# stepper-encoder-lcd.net
KiCad netlist of a schematic drawn in Altium Designer
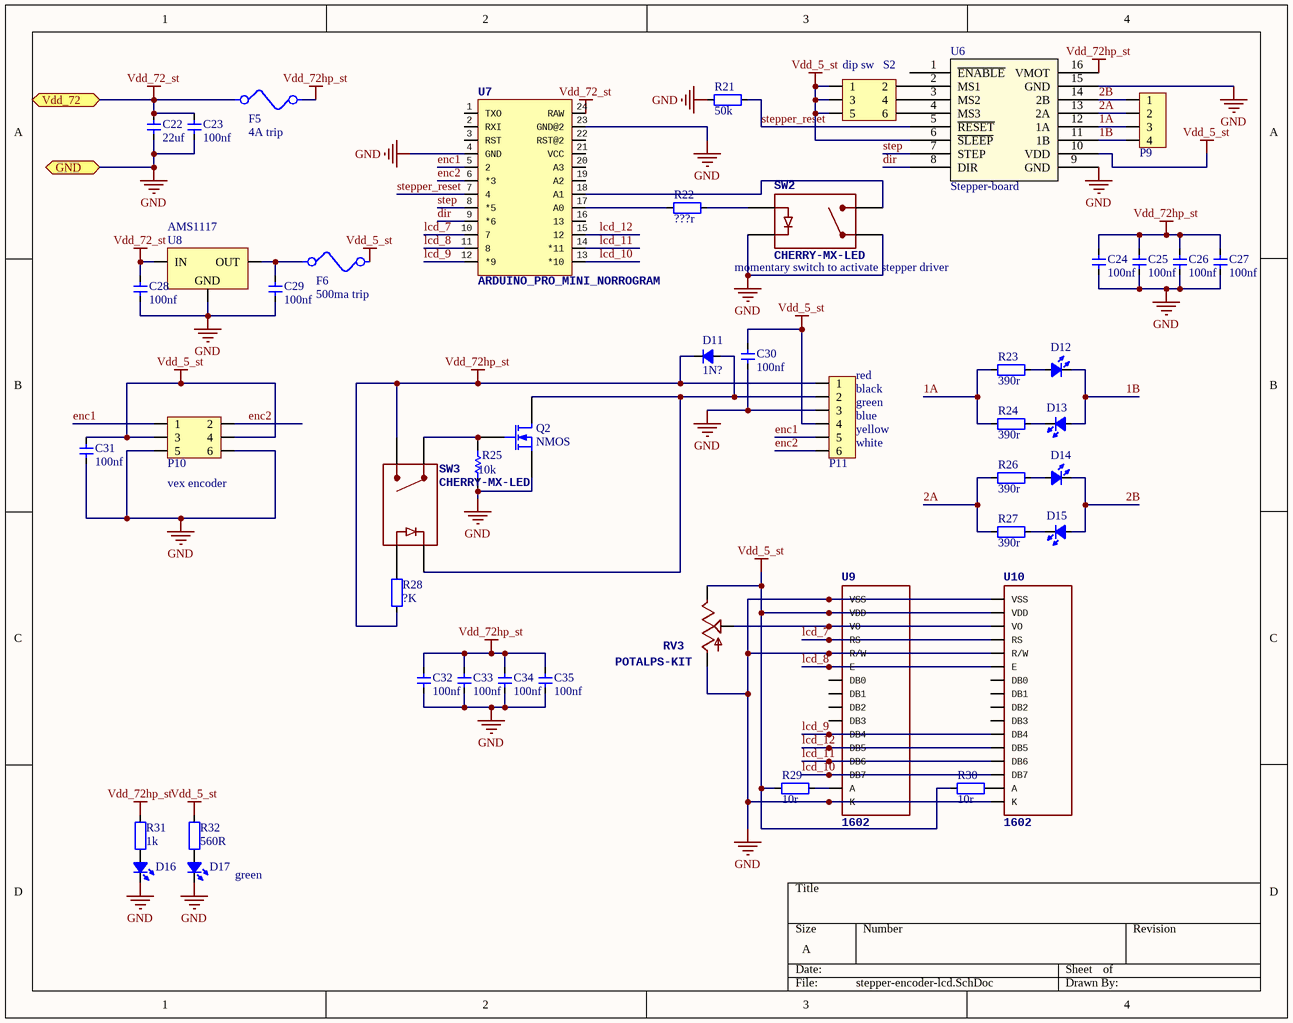
[diagram p0: stepper-encoder-lcd.SchDoc]

(export (version "E")
  (design (tool "Eeschema 10.0.6"))
  (components
    (comp (ref "C22")
      (value "22uf")
      (footprint "PCB_PassiveCap:CAP_0805")
      (description "Capacitor")
      (fields (field (name "Comment") "Cap_0805"))
      (libsource (lib "SCH_Passive") (part "Cap_0805"))
    )
    (comp (ref "C23")
      (value "100nf")
      (footprint "PCB_PassiveCap:CAP_0805")
      (description "Capacitor")
      (fields (field (name "Comment") "Cap_0805"))
      (libsource (lib "SCH_Passive") (part "Cap_0805"))
    )
    (comp (ref "C24")
      (value "100nf")
      (footprint "PCB_PassiveCap:CAP_0805")
      (description "Capacitor")
      (fields (field (name "Comment") "Cap_0805"))
      (libsource (lib "SCH_Passive") (part "Cap_0805"))
    )
    (comp (ref "C25")
      (value "100nf")
      (footprint "PCB_PassiveCap:CAP_0805")
      (description "Capacitor")
      (fields (field (name "Comment") "Cap_0805"))
      (libsource (lib "SCH_Passive") (part "Cap_0805"))
    )
    (comp (ref "C26")
      (value "100nf")
      (footprint "PCB_PassiveCap:CAP_0805")
      (description "Capacitor")
      (fields (field (name "Comment") "Cap_0805"))
      (libsource (lib "SCH_Passive") (part "Cap_0805"))
    )
    (comp (ref "C27")
      (value "100nf")
      (footprint "PCB_PassiveCap:CAP_0805")
      (description "Capacitor")
      (fields (field (name "Comment") "Cap_0805"))
      (libsource (lib "SCH_Passive") (part "Cap_0805"))
    )
    (comp (ref "C28")
      (value "100nf")
      (footprint "PCB_PassiveCap:CAP_0805")
      (description "Capacitor")
      (fields (field (name "Comment") "Cap_0805"))
      (libsource (lib "SCH_Passive") (part "Cap_0805"))
    )
    (comp (ref "C29")
      (value "100nf")
      (footprint "PCB_PassiveCap:CAP_0805")
      (description "Capacitor")
      (fields (field (name "Comment") "Cap_0805"))
      (libsource (lib "SCH_Passive") (part "Cap_0805"))
    )
    (comp (ref "C30")
      (value "100nf")
      (footprint "PCB_PassiveCap:CAP_0805")
      (description "Capacitor")
      (fields (field (name "Comment") "Cap_0805"))
      (libsource (lib "SCH_Passive") (part "Cap_0805"))
    )
    (comp (ref "C31")
      (value "100nf")
      (footprint "PCB_PassiveCap:CAP_0805")
      (description "Capacitor")
      (fields (field (name "Comment") "Cap_0805"))
      (libsource (lib "SCH_Passive") (part "Cap_0805"))
    )
    (comp (ref "C32")
      (value "100nf")
      (footprint "PCB_PassiveCap:CAP_0805")
      (description "Capacitor")
      (fields (field (name "Comment") "Cap_0805"))
      (libsource (lib "SCH_Passive") (part "Cap_0805"))
    )
    (comp (ref "C33")
      (value "100nf")
      (footprint "PCB_PassiveCap:CAP_0805")
      (description "Capacitor")
      (fields (field (name "Comment") "Cap_0805"))
      (libsource (lib "SCH_Passive") (part "Cap_0805"))
    )
    (comp (ref "C34")
      (value "100nf")
      (footprint "PCB_PassiveCap:CAP_0805")
      (description "Capacitor")
      (fields (field (name "Comment") "Cap_0805"))
      (libsource (lib "SCH_Passive") (part "Cap_0805"))
    )
    (comp (ref "C35")
      (value "100nf")
      (footprint "PCB_PassiveCap:CAP_0805")
      (description "Capacitor")
      (fields (field (name "Comment") "Cap_0805"))
      (libsource (lib "SCH_Passive") (part "Cap_0805"))
    )
    (comp (ref "D11")
      (value "1N?")
      (footprint "PCB_ActiveDIO:SOD-323")
      (description "Diode")
      (fields (field (name "Comment") "Diode_SOD323"))
      (libsource (lib "SCH_Active") (part "Diode_SOD323"))
    )
    (comp (ref "D12")
      (value "LED_0805")
      (footprint "PCB_ActiveLED:LED_0805_YELLOW")
      (description "LED")
      (libsource (lib "SCH_Active") (part "LED_0805"))
    )
    (comp (ref "D13")
      (value "LED_0805")
      (footprint "PCB_ActiveLED:LED_0805_YELLOW")
      (description "LED")
      (libsource (lib "SCH_Active") (part "LED_0805"))
    )
    (comp (ref "D14")
      (value "LED_0805")
      (footprint "PCB_ActiveLED:LED_0805_YELLOW")
      (description "LED")
      (libsource (lib "SCH_Active") (part "LED_0805"))
    )
    (comp (ref "D15")
      (value "LED_0805")
      (footprint "PCB_ActiveLED:LED_0805_YELLOW")
      (description "LED")
      (libsource (lib "SCH_Active") (part "LED_0805"))
    )
    (comp (ref "D16")
      (value "LED_0805")
      (footprint "PCB_ActiveLED:LED_0805_RED")
      (description "LED")
      (libsource (lib "SCH_Active") (part "LED_0805"))
    )
    (comp (ref "D17")
      (value "LED_0805")
      (footprint "PCB_ActiveLED:LED_0805_RED")
      (description "LED")
      (libsource (lib "SCH_Active") (part "LED_0805"))
    )
    (comp (ref "F5")
      (value "4A trip")
      (footprint "Multifuse1812")
      (description "RO ZEK MULTI 500MA SMD 1812 MF-MSMF050-2 BOURNS")
      (fields (field (name "MFG") "BOURNS"))
      (libsource (lib "Ultimaker") (part "Multifuse"))
    )
    (comp (ref "F6")
      (value "500ma trip")
      (footprint "Multifuse1812")
      (description "RO ZEK MULTI 500MA SMD 1812 MF-MSMF050-2 BOURNS")
      (fields (field (name "MFG") "BOURNS"))
      (libsource (lib "Ultimaker") (part "Multifuse"))
    )
    (comp (ref "P9")
      (value "HDR1x4_2.54")
      (footprint "PCB_ConnectorHDR:HDR1x4_2.54_180")
      (description "Header")
      (libsource (lib "SCH_ConnectorHDR") (part "HDR1x4_2.54"))
    )
    (comp (ref "P10")
      (value "HDR2x3_2.54")
      (footprint "PCB_ConnectorHDR:HDR2X3_2.54_180")
      (description "Header")
      (libsource (lib "SCH_ConnectorHDR") (part "HDR2x3_2.54"))
    )
    (comp (ref "P11")
      (value "HDR1x6_2.54")
      (footprint "PCB_ConnectorHDR:HDR1X6_2.54_180")
      (description "Header")
      (libsource (lib "SCH_ConnectorHDR") (part "HDR1x6_2.54"))
    )
    (comp (ref "Q2")
      (value "NMOS")
      (footprint "SOT23-3")
      (description "N-Channel MOSFET")
      (fields (field (name "PUBLISHER") "Altium Limited"))
      (libsource (lib "Miscellaneous Devices") (part "MOSFET-N"))
    )
    (comp (ref "R21")
      (value "50k")
      (footprint "PCB_PassiveRes:RES_0805")
      (description "Resistor")
      (fields (field (name "Comment") "Res_0805"))
      (libsource (lib "SCH_Passive") (part "Res_0805"))
    )
    (comp (ref "R22")
      (value "???r")
      (footprint "PCB_PassiveRes:RES_0805")
      (description "Resistor")
      (fields (field (name "Comment") "Res_0805"))
      (libsource (lib "SCH_Passive") (part "Res_0805"))
    )
    (comp (ref "R23")
      (value "390r")
      (footprint "PCB_PassiveRes:RES_0805")
      (description "Resistor")
      (fields (field (name "Comment") "Res_0805"))
      (libsource (lib "SCH_Passive") (part "Res_0805"))
    )
    (comp (ref "R24")
      (value "390r")
      (footprint "PCB_PassiveRes:RES_0805")
      (description "Resistor")
      (fields (field (name "Comment") "Res_0805"))
      (libsource (lib "SCH_Passive") (part "Res_0805"))
    )
    (comp (ref "R25")
      (value "10k")
      (footprint "RES_0805")
      (description "Resistor")
      (fields (field (name "Comment") "R2") (field (name "PUBLISHER") "Altium Limited"))
      (libsource (lib "Miscellaneous Devices") (part "Res1"))
    )
    (comp (ref "R26")
      (value "390r")
      (footprint "PCB_PassiveRes:RES_0805")
      (description "Resistor")
      (fields (field (name "Comment") "Res_0805"))
      (libsource (lib "SCH_Passive") (part "Res_0805"))
    )
    (comp (ref "R27")
      (value "390r")
      (footprint "PCB_PassiveRes:RES_0805")
      (description "Resistor")
      (fields (field (name "Comment") "Res_0805"))
      (libsource (lib "SCH_Passive") (part "Res_0805"))
    )
    (comp (ref "R28")
      (value "?K")
      (footprint "PCB_PassiveRes:RES_0805")
      (description "Resistor")
      (fields (field (name "Comment") "Res_0805"))
      (libsource (lib "") (part "Res_0805_1"))
    )
    (comp (ref "R29")
      (value "10r")
      (footprint "PCB_PassiveRes:RES_0805")
      (description "Resistor")
      (fields (field (name "Comment") "Res_0805"))
      (libsource (lib "SCH_Passive") (part "Res_0805"))
    )
    (comp (ref "R30")
      (value "10r")
      (footprint "PCB_PassiveRes:RES_0805")
      (description "Resistor")
      (fields (field (name "Comment") "Res_0805"))
      (libsource (lib "SCH_Passive") (part "Res_0805"))
    )
    (comp (ref "R31")
      (value "1k")
      (footprint "PCB_PassiveRes:RES_0805")
      (description "Resistor")
      (fields (field (name "Comment") "Res_0805"))
      (libsource (lib "") (part "Res_0805_1"))
    )
    (comp (ref "R32")
      (value "560R")
      (footprint "PCB_PassiveRes:RES_0805")
      (description "Resistor")
      (fields (field (name "Comment") "Res_0805"))
      (libsource (lib "") (part "Res_0805_1"))
    )
    (comp (ref "RV3")
      (value "POTALPS-KIT")
      (footprint "Bourns-slimline-axialbracket")
      (libsource (lib "SparkFun-Electromechanical") (part "POTALPS-KIT"))
    )
    (comp (ref "S2")
      (value "HDR2x3_2.54")
      (footprint "DIP6")
      (description "Header")
      (libsource (lib "SCH_ConnectorHDR") (part "HDR2x3_2.54"))
    )
    (comp (ref "SW2")
      (value "CHERRY-MX-LED")
      (footprint "MX-LED")
      (libsource (lib "cherry-switches") (part "CHERRY-MX-LED"))
    )
    (comp (ref "SW3")
      (value "CHERRY-MX-LED")
      (footprint "MX-LED")
      (libsource (lib "cherry-switches") (part "CHERRY-MX-LED"))
    )
    (comp (ref "U6")
      (value "Stepper-board")
      (footprint "stepper-board")
      (libsource (lib "Schlib1") (part "Stepper-board"))
    )
    (comp (ref "U7")
      (value "ARDUINO_PRO_MINI_NORROGRAM")
      (footprint "ARDUINO_PRO_MINI_NOPROGRAM")
      (libsource (lib "SparkFun-Boards") (part "ARDUINO_PRO_MINI_NORROGRAM"))
    )
    (comp (ref "U8")
      (value "AMS1117")
      (footprint "SOT223-3-CONNECTEDTAB")
      (description "Power")
      (libsource (lib "SCH_IntegratedCircuit") (part "AMS1117"))
    )
    (comp (ref "U9")
      (value "1602")
      (footprint "LCD-16X2_NOSILK")
      (libsource (lib "SparkFun-Displays") (part "LCD-16X2NOSILK"))
    )
    (comp (ref "U10")
      (value "1602")
      (footprint "LCD-16X2_NOSILK")
      (libsource (lib "SparkFun-Displays") (part "LCD-16X2NOSILK"))
    )
  )
  (nets
    (net (code "1") (name "/1A") (class "Default")
      (node (ref "P9") (pin "3") (pinfunction "3_3") (pintype "passive"))
      (node (ref "R23") (pin "1") (pinfunction "1_1") (pintype "passive"))
      (node (ref "R24") (pin "1") (pinfunction "1_1") (pintype "passive"))
      (node (ref "U6") (pin "12") (pinfunction "1A_12") (pintype "passive"))
    )
    (net (code "2") (name "/1B") (class "Default")
      (node (ref "D12") (pin "2") (pinfunction "K_2") (pintype "passive"))
      (node (ref "D13") (pin "1") (pinfunction "A_1") (pintype "passive"))
      (node (ref "P9") (pin "4") (pinfunction "4_4") (pintype "passive"))
      (node (ref "U6") (pin "11") (pinfunction "1B_11") (pintype "passive"))
    )
    (net (code "3") (name "/2A") (class "Default")
      (node (ref "P9") (pin "2") (pinfunction "2_2") (pintype "passive"))
      (node (ref "R26") (pin "1") (pinfunction "1_1") (pintype "passive"))
      (node (ref "R27") (pin "1") (pinfunction "1_1") (pintype "passive"))
      (node (ref "U6") (pin "13") (pinfunction "2A_13") (pintype "passive"))
    )
    (net (code "4") (name "/2B") (class "Default")
      (node (ref "D14") (pin "2") (pinfunction "K_2") (pintype "passive"))
      (node (ref "D15") (pin "1") (pinfunction "A_1") (pintype "passive"))
      (node (ref "P9") (pin "1") (pinfunction "1_1") (pintype "passive"))
      (node (ref "U6") (pin "14") (pinfunction "2B_14") (pintype "passive"))
    )
    (net (code "5") (name "/dir") (class "Default")
      (node (ref "U6") (pin "8") (pinfunction "DIR_8") (pintype "passive"))
      (node (ref "U7") (pin "9") (pinfunction "*6_9") (pintype "passive"))
    )
    (net (code "6") (name "/enc1") (class "Default")
      (node (ref "P10") (pin "1") (pinfunction "1_1") (pintype "passive"))
      (node (ref "P11") (pin "5") (pinfunction "5_5") (pintype "passive"))
      (node (ref "U7") (pin "5") (pinfunction "2_5") (pintype "passive"))
    )
    (net (code "7") (name "/enc2") (class "Default")
      (node (ref "P10") (pin "2") (pinfunction "2_2") (pintype "passive"))
      (node (ref "P11") (pin "6") (pinfunction "6_6") (pintype "passive"))
      (node (ref "U7") (pin "6") (pinfunction "*3_6") (pintype "passive"))
    )
    (net (code "8") (name "/lcd_7") (class "Default")
      (node (ref "U10") (pin "4") (pinfunction "RS_4") (pintype "passive"))
      (node (ref "U7") (pin "10") (pinfunction "7_10") (pintype "passive"))
      (node (ref "U9") (pin "4") (pinfunction "RS_4") (pintype "passive"))
    )
    (net (code "9") (name "/lcd_8") (class "Default")
      (node (ref "U10") (pin "6") (pinfunction "E_6") (pintype "passive"))
      (node (ref "U7") (pin "11") (pinfunction "8_11") (pintype "passive"))
      (node (ref "U9") (pin "6") (pinfunction "E_6") (pintype "passive"))
    )
    (net (code "10") (name "/lcd_9") (class "Default")
      (node (ref "U10") (pin "11") (pinfunction "DB4_11") (pintype "passive"))
      (node (ref "U7") (pin "12") (pinfunction "*9_12") (pintype "passive"))
      (node (ref "U9") (pin "11") (pinfunction "DB4_11") (pintype "passive"))
    )
    (net (code "11") (name "/lcd_10") (class "Default")
      (node (ref "U10") (pin "14") (pinfunction "DB7_14") (pintype "passive"))
      (node (ref "U7") (pin "13") (pinfunction "*10_13") (pintype "passive"))
      (node (ref "U9") (pin "14") (pinfunction "DB7_14") (pintype "passive"))
    )
    (net (code "12") (name "/lcd_11") (class "Default")
      (node (ref "U10") (pin "13") (pinfunction "DB6_13") (pintype "passive"))
      (node (ref "U7") (pin "14") (pinfunction "*11_14") (pintype "passive"))
      (node (ref "U9") (pin "13") (pinfunction "DB6_13") (pintype "passive"))
    )
    (net (code "13") (name "/lcd_12") (class "Default")
      (node (ref "U10") (pin "12") (pinfunction "DB5_12") (pintype "passive"))
      (node (ref "U7") (pin "15") (pinfunction "12_15") (pintype "passive"))
      (node (ref "U9") (pin "12") (pinfunction "DB5_12") (pintype "passive"))
    )
    (net (code "14") (name "/step") (class "Default")
      (node (ref "U6") (pin "7") (pinfunction "STEP_7") (pintype "passive"))
      (node (ref "U7") (pin "8") (pinfunction "*5_8") (pintype "passive"))
    )
    (net (code "15") (name "/stepper_reset") (class "Default")
      (node (ref "R21") (pin "2") (pinfunction "2_2") (pintype "passive"))
      (node (ref "U6") (pin "5") (pinfunction "~{RESET}_5") (pintype "passive"))
      (node (ref "U7") (pin "7") (pinfunction "4_7") (pintype "passive"))
    )
    (net (code "16") (name "GND") (class "Default")
      (node (ref "C22") (pin "1") (pinfunction "1_1") (pintype "passive"))
      (node (ref "C23") (pin "1") (pinfunction "1_1") (pintype "passive"))
      (node (ref "C24") (pin "2") (pinfunction "2_2") (pintype "passive"))
      (node (ref "C25") (pin "2") (pinfunction "2_2") (pintype "passive"))
      (node (ref "C26") (pin "2") (pinfunction "2_2") (pintype "passive"))
      (node (ref "C27") (pin "2") (pinfunction "2_2") (pintype "passive"))
      (node (ref "C28") (pin "1") (pinfunction "1_1") (pintype "passive"))
      (node (ref "C29") (pin "1") (pinfunction "1_1") (pintype "passive"))
      (node (ref "C30") (pin "2") (pinfunction "2_2") (pintype "passive"))
      (node (ref "C31") (pin "2") (pinfunction "2_2") (pintype "passive"))
      (node (ref "C32") (pin "2") (pinfunction "2_2") (pintype "passive"))
      (node (ref "C33") (pin "2") (pinfunction "2_2") (pintype "passive"))
      (node (ref "C34") (pin "2") (pinfunction "2_2") (pintype "passive"))
      (node (ref "C35") (pin "2") (pinfunction "2_2") (pintype "passive"))
      (node (ref "D16") (pin "2") (pinfunction "K_2") (pintype "passive"))
      (node (ref "D17") (pin "2") (pinfunction "K_2") (pintype "passive"))
      (node (ref "P10") (pin "5") (pinfunction "5_5") (pintype "passive"))
      (node (ref "P10") (pin "6") (pinfunction "6_6") (pintype "passive"))
      (node (ref "P11") (pin "3") (pinfunction "3_3") (pintype "passive"))
      (node (ref "Q2") (pin "3") (pinfunction "S_3") (pintype "passive"))
      (node (ref "R21") (pin "1") (pinfunction "1_1") (pintype "passive"))
      (node (ref "R25") (pin "1") (pinfunction "1_1") (pintype "passive"))
      (node (ref "RV3") (pin "P$3") (pinfunction "A_P$3") (pintype "passive"))
      (node (ref "SW2") (pin "P$1") (pinfunction "1_P$1") (pintype "passive"))
      (node (ref "SW2") (pin "P$3") (pinfunction "P$3_P$3") (pintype "passive"))
      (node (ref "U10") (pin "1") (pinfunction "VSS_1") (pintype "power_in"))
      (node (ref "U10") (pin "16") (pinfunction "K_16") (pintype "power_in"))
      (node (ref "U10") (pin "5") (pinfunction "R/W_5") (pintype "passive"))
      (node (ref "U6") (pin "15") (pinfunction "GND_15") (pintype "passive"))
      (node (ref "U6") (pin "9") (pinfunction "GND_9") (pintype "passive"))
      (node (ref "U7") (pin "23") (pinfunction "GND@2_23") (pintype "passive"))
      (node (ref "U7") (pin "4") (pinfunction "GND_4") (pintype "passive"))
      (node (ref "U8") (pin "1") (pinfunction "GND_1") (pintype "power_in"))
      (node (ref "U9") (pin "1") (pinfunction "VSS_1") (pintype "power_in"))
      (node (ref "U9") (pin "16") (pinfunction "K_16") (pintype "power_in"))
      (node (ref "U9") (pin "5") (pinfunction "R/W_5") (pintype "passive"))
    )
    (net (code "17") (name "Net-(D11-A)") (class "Default")
      (node (ref "D11") (pin "1") (pinfunction "A_1") (pintype "passive"))
      (node (ref "P11") (pin "2") (pinfunction "2_2") (pintype "passive"))
      (node (ref "Q2") (pin "1") (pinfunction "D_1") (pintype "passive"))
      (node (ref "SW3") (pin "P$3") (pinfunction "P$3_P$3") (pintype "passive"))
    )
    (net (code "18") (name "Net-(D12-A)") (class "Default")
      (node (ref "D12") (pin "1") (pinfunction "A_1") (pintype "passive"))
      (node (ref "R23") (pin "2") (pinfunction "2_2") (pintype "passive"))
    )
    (net (code "19") (name "Net-(D13-K)") (class "Default")
      (node (ref "D13") (pin "2") (pinfunction "K_2") (pintype "passive"))
      (node (ref "R24") (pin "2") (pinfunction "2_2") (pintype "passive"))
    )
    (net (code "20") (name "Net-(D14-A)") (class "Default")
      (node (ref "D14") (pin "1") (pinfunction "A_1") (pintype "passive"))
      (node (ref "R26") (pin "2") (pinfunction "2_2") (pintype "passive"))
    )
    (net (code "21") (name "Net-(D15-K)") (class "Default")
      (node (ref "D15") (pin "2") (pinfunction "K_2") (pintype "passive"))
      (node (ref "R27") (pin "2") (pinfunction "2_2") (pintype "passive"))
    )
    (net (code "22") (name "Net-(D16-A)") (class "Default")
      (node (ref "D16") (pin "1") (pinfunction "A_1") (pintype "passive"))
      (node (ref "R31") (pin "1") (pinfunction "1_1") (pintype "passive"))
    )
    (net (code "23") (name "Net-(D17-A)") (class "Default")
      (node (ref "D17") (pin "1") (pinfunction "A_1") (pintype "passive"))
      (node (ref "R32") (pin "1") (pinfunction "1_1") (pintype "passive"))
    )
    (net (code "24") (name "Net-(Q2-G)") (class "Default")
      (node (ref "Q2") (pin "2") (pinfunction "G_2") (pintype "passive"))
      (node (ref "R25") (pin "2") (pinfunction "2_2") (pintype "passive"))
      (node (ref "SW3") (pin "P$1") (pinfunction "1_P$1") (pintype "passive"))
    )
    (net (code "25") (name "Net-(R22-Pad2)") (class "Default")
      (node (ref "R22") (pin "2") (pinfunction "2_2") (pintype "passive"))
      (node (ref "SW2") (pin "P$4") (pinfunction "P$4_P$4") (pintype "passive"))
    )
    (net (code "26") (name "Net-(R28-Pad2)") (class "Default")
      (node (ref "R28") (pin "2") (pinfunction "2_2") (pintype "passive"))
      (node (ref "SW3") (pin "P$4") (pinfunction "P$4_P$4") (pintype "passive"))
    )
    (net (code "27") (name "Net-(RV3-S)") (class "Default")
      (node (ref "RV3") (pin "P$2") (pinfunction "S_P$2") (pintype "passive"))
      (node (ref "U10") (pin "3") (pinfunction "VO_3") (pintype "passive"))
      (node (ref "U9") (pin "3") (pinfunction "VO_3") (pintype "passive"))
    )
    (net (code "28") (name "Net-(SW2-2)") (class "Default")
      (node (ref "SW2") (pin "P$2") (pinfunction "2_P$2") (pintype "passive"))
      (node (ref "U7") (pin "18") (pinfunction "A1_18") (pintype "passive"))
    )
    (net (code "29") (name "Net-(U6-MS1)") (class "Default")
      (node (ref "S2") (pin "2") (pinfunction "2_2") (pintype "passive"))
      (node (ref "U6") (pin "2") (pinfunction "MS1_2") (pintype "passive"))
    )
    (net (code "30") (name "Net-(U6-MS2)") (class "Default")
      (node (ref "S2") (pin "4") (pinfunction "4_4") (pintype "passive"))
      (node (ref "U6") (pin "3") (pinfunction "MS2_3") (pintype "passive"))
    )
    (net (code "31") (name "Net-(U6-MS3)") (class "Default")
      (node (ref "S2") (pin "6") (pinfunction "6_6") (pintype "passive"))
      (node (ref "U6") (pin "4") (pinfunction "MS3_4") (pintype "passive"))
    )
    (net (code "32") (name "Net-(U7-A0)") (class "Default")
      (node (ref "R22") (pin "1") (pinfunction "1_1") (pintype "passive"))
      (node (ref "U7") (pin "17") (pinfunction "A0_17") (pintype "passive"))
    )
    (net (code "33") (name "Net-(U8-OUT)") (class "Default")
      (node (ref "C29") (pin "2") (pinfunction "2_2") (pintype "passive"))
      (node (ref "F6") (pin "1") (pinfunction "1_1") (pintype "passive"))
      (node (ref "U8") (pin "2") (pinfunction "OUT_2") (pintype "power_in"))
    )
    (net (code "34") (name "Net-(U9-A)") (class "Default")
      (node (ref "R29") (pin "2") (pinfunction "2_2") (pintype "passive"))
      (node (ref "U9") (pin "15") (pinfunction "A_15") (pintype "power_in"))
    )
    (net (code "35") (name "Net-(U10-A)") (class "Default")
      (node (ref "R30") (pin "2") (pinfunction "2_2") (pintype "passive"))
      (node (ref "U10") (pin "15") (pinfunction "A_15") (pintype "power_in"))
    )
    (net (code "36") (name "Vdd_5_st") (class "Default")
      (node (ref "C30") (pin "1") (pinfunction "1_1") (pintype "passive"))
      (node (ref "C31") (pin "1") (pinfunction "1_1") (pintype "passive"))
      (node (ref "F6") (pin "2") (pinfunction "2_2") (pintype "passive"))
      (node (ref "P10") (pin "3") (pinfunction "3_3") (pintype "passive"))
      (node (ref "P10") (pin "4") (pinfunction "4_4") (pintype "passive"))
      (node (ref "P11") (pin "4") (pinfunction "4_4") (pintype "passive"))
      (node (ref "R29") (pin "1") (pinfunction "1_1") (pintype "passive"))
      (node (ref "R30") (pin "1") (pinfunction "1_1") (pintype "passive"))
      (node (ref "R32") (pin "2") (pinfunction "2_2") (pintype "passive"))
      (node (ref "RV3") (pin "P$1") (pinfunction "E_P$1") (pintype "passive"))
      (node (ref "S2") (pin "1") (pinfunction "1_1") (pintype "passive"))
      (node (ref "S2") (pin "3") (pinfunction "3_3") (pintype "passive"))
      (node (ref "S2") (pin "5") (pinfunction "5_5") (pintype "passive"))
      (node (ref "U10") (pin "2") (pinfunction "VDD_2") (pintype "power_in"))
      (node (ref "U6") (pin "10") (pinfunction "VDD_10") (pintype "passive"))
      (node (ref "U6") (pin "6") (pinfunction "~{SLEEP}_6") (pintype "passive"))
      (node (ref "U9") (pin "2") (pinfunction "VDD_2") (pintype "power_in"))
    )
    (net (code "37") (name "Vdd_72_st") (class "Default")
      (node (ref "C22") (pin "2") (pinfunction "2_2") (pintype "passive"))
      (node (ref "C23") (pin "2") (pinfunction "2_2") (pintype "passive"))
      (node (ref "C28") (pin "2") (pinfunction "2_2") (pintype "passive"))
      (node (ref "F5") (pin "1") (pinfunction "1_1") (pintype "passive"))
      (node (ref "U7") (pin "24") (pinfunction "RAW_24") (pintype "passive"))
      (node (ref "U8") (pin "3") (pinfunction "IN_3") (pintype "power_in"))
    )
    (net (code "38") (name "Vdd_72hp_st") (class "Default")
      (node (ref "C24") (pin "1") (pinfunction "1_1") (pintype "passive"))
      (node (ref "C25") (pin "1") (pinfunction "1_1") (pintype "passive"))
      (node (ref "C26") (pin "1") (pinfunction "1_1") (pintype "passive"))
      (node (ref "C27") (pin "1") (pinfunction "1_1") (pintype "passive"))
      (node (ref "C32") (pin "1") (pinfunction "1_1") (pintype "passive"))
      (node (ref "C33") (pin "1") (pinfunction "1_1") (pintype "passive"))
      (node (ref "C34") (pin "1") (pinfunction "1_1") (pintype "passive"))
      (node (ref "C35") (pin "1") (pinfunction "1_1") (pintype "passive"))
      (node (ref "D11") (pin "2") (pinfunction "K_2") (pintype "passive"))
      (node (ref "F5") (pin "2") (pinfunction "2_2") (pintype "passive"))
      (node (ref "P11") (pin "1") (pinfunction "1_1") (pintype "passive"))
      (node (ref "R28") (pin "1") (pinfunction "1_1") (pintype "passive"))
      (node (ref "R31") (pin "2") (pinfunction "2_2") (pintype "passive"))
      (node (ref "SW3") (pin "P$2") (pinfunction "2_P$2") (pintype "passive"))
      (node (ref "U6") (pin "16") (pinfunction "VMOT_16") (pintype "passive"))
    )
    (net (code "39") (name "unconnected-(U6-~{ENABLE}-Pad1)") (class "Default")
      (node (ref "U6") (pin "1") (pinfunction "~{ENABLE}_1") (pintype "passive"))
    )
    (net (code "40") (name "unconnected-(U7-13-Pad16)") (class "Default")
      (node (ref "U7") (pin "16") (pinfunction "13_16") (pintype "passive"))
    )
    (net (code "41") (name "unconnected-(U7-A2-Pad19)") (class "Default")
      (node (ref "U7") (pin "19") (pinfunction "A2_19") (pintype "passive"))
    )
    (net (code "42") (name "unconnected-(U7-A3-Pad20)") (class "Default")
      (node (ref "U7") (pin "20") (pinfunction "A3_20") (pintype "passive"))
    )
    (net (code "43") (name "unconnected-(U7-RST-Pad3)") (class "Default")
      (node (ref "U7") (pin "3") (pinfunction "RST_3") (pintype "passive"))
    )
    (net (code "44") (name "unconnected-(U7-RST@2-Pad22)") (class "Default")
      (node (ref "U7") (pin "22") (pinfunction "RST@2_22") (pintype "passive"))
    )
    (net (code "45") (name "unconnected-(U7-RXI-Pad2)") (class "Default")
      (node (ref "U7") (pin "2") (pinfunction "RXI_2") (pintype "passive"))
    )
    (net (code "46") (name "unconnected-(U7-TXO-Pad1)") (class "Default")
      (node (ref "U7") (pin "1") (pinfunction "TXO_1") (pintype "passive"))
    )
    (net (code "47") (name "unconnected-(U7-VCC-Pad21)") (class "Default")
      (node (ref "U7") (pin "21") (pinfunction "VCC_21") (pintype "passive"))
    )
    (net (code "48") (name "unconnected-(U9-DB0-Pad7)") (class "Default")
      (node (ref "U9") (pin "7") (pinfunction "DB0_7") (pintype "passive"))
    )
    (net (code "49") (name "unconnected-(U9-DB1-Pad8)") (class "Default")
      (node (ref "U9") (pin "8") (pinfunction "DB1_8") (pintype "passive"))
    )
    (net (code "50") (name "unconnected-(U9-DB2-Pad9)") (class "Default")
      (node (ref "U9") (pin "9") (pinfunction "DB2_9") (pintype "passive"))
    )
    (net (code "51") (name "unconnected-(U9-DB3-Pad10)") (class "Default")
      (node (ref "U9") (pin "10") (pinfunction "DB3_10") (pintype "passive"))
    )
    (net (code "52") (name "unconnected-(U10-DB0-Pad7)") (class "Default")
      (node (ref "U10") (pin "7") (pinfunction "DB0_7") (pintype "passive"))
    )
    (net (code "53") (name "unconnected-(U10-DB1-Pad8)") (class "Default")
      (node (ref "U10") (pin "8") (pinfunction "DB1_8") (pintype "passive"))
    )
    (net (code "54") (name "unconnected-(U10-DB2-Pad9)") (class "Default")
      (node (ref "U10") (pin "9") (pinfunction "DB2_9") (pintype "passive"))
    )
    (net (code "55") (name "unconnected-(U10-DB3-Pad10)") (class "Default")
      (node (ref "U10") (pin "10") (pinfunction "DB3_10") (pintype "passive"))
    )
  )
)
